# 2017_FDP_STRATEGIE.net
KiCad netlist of a schematic drawn in Altium Designer
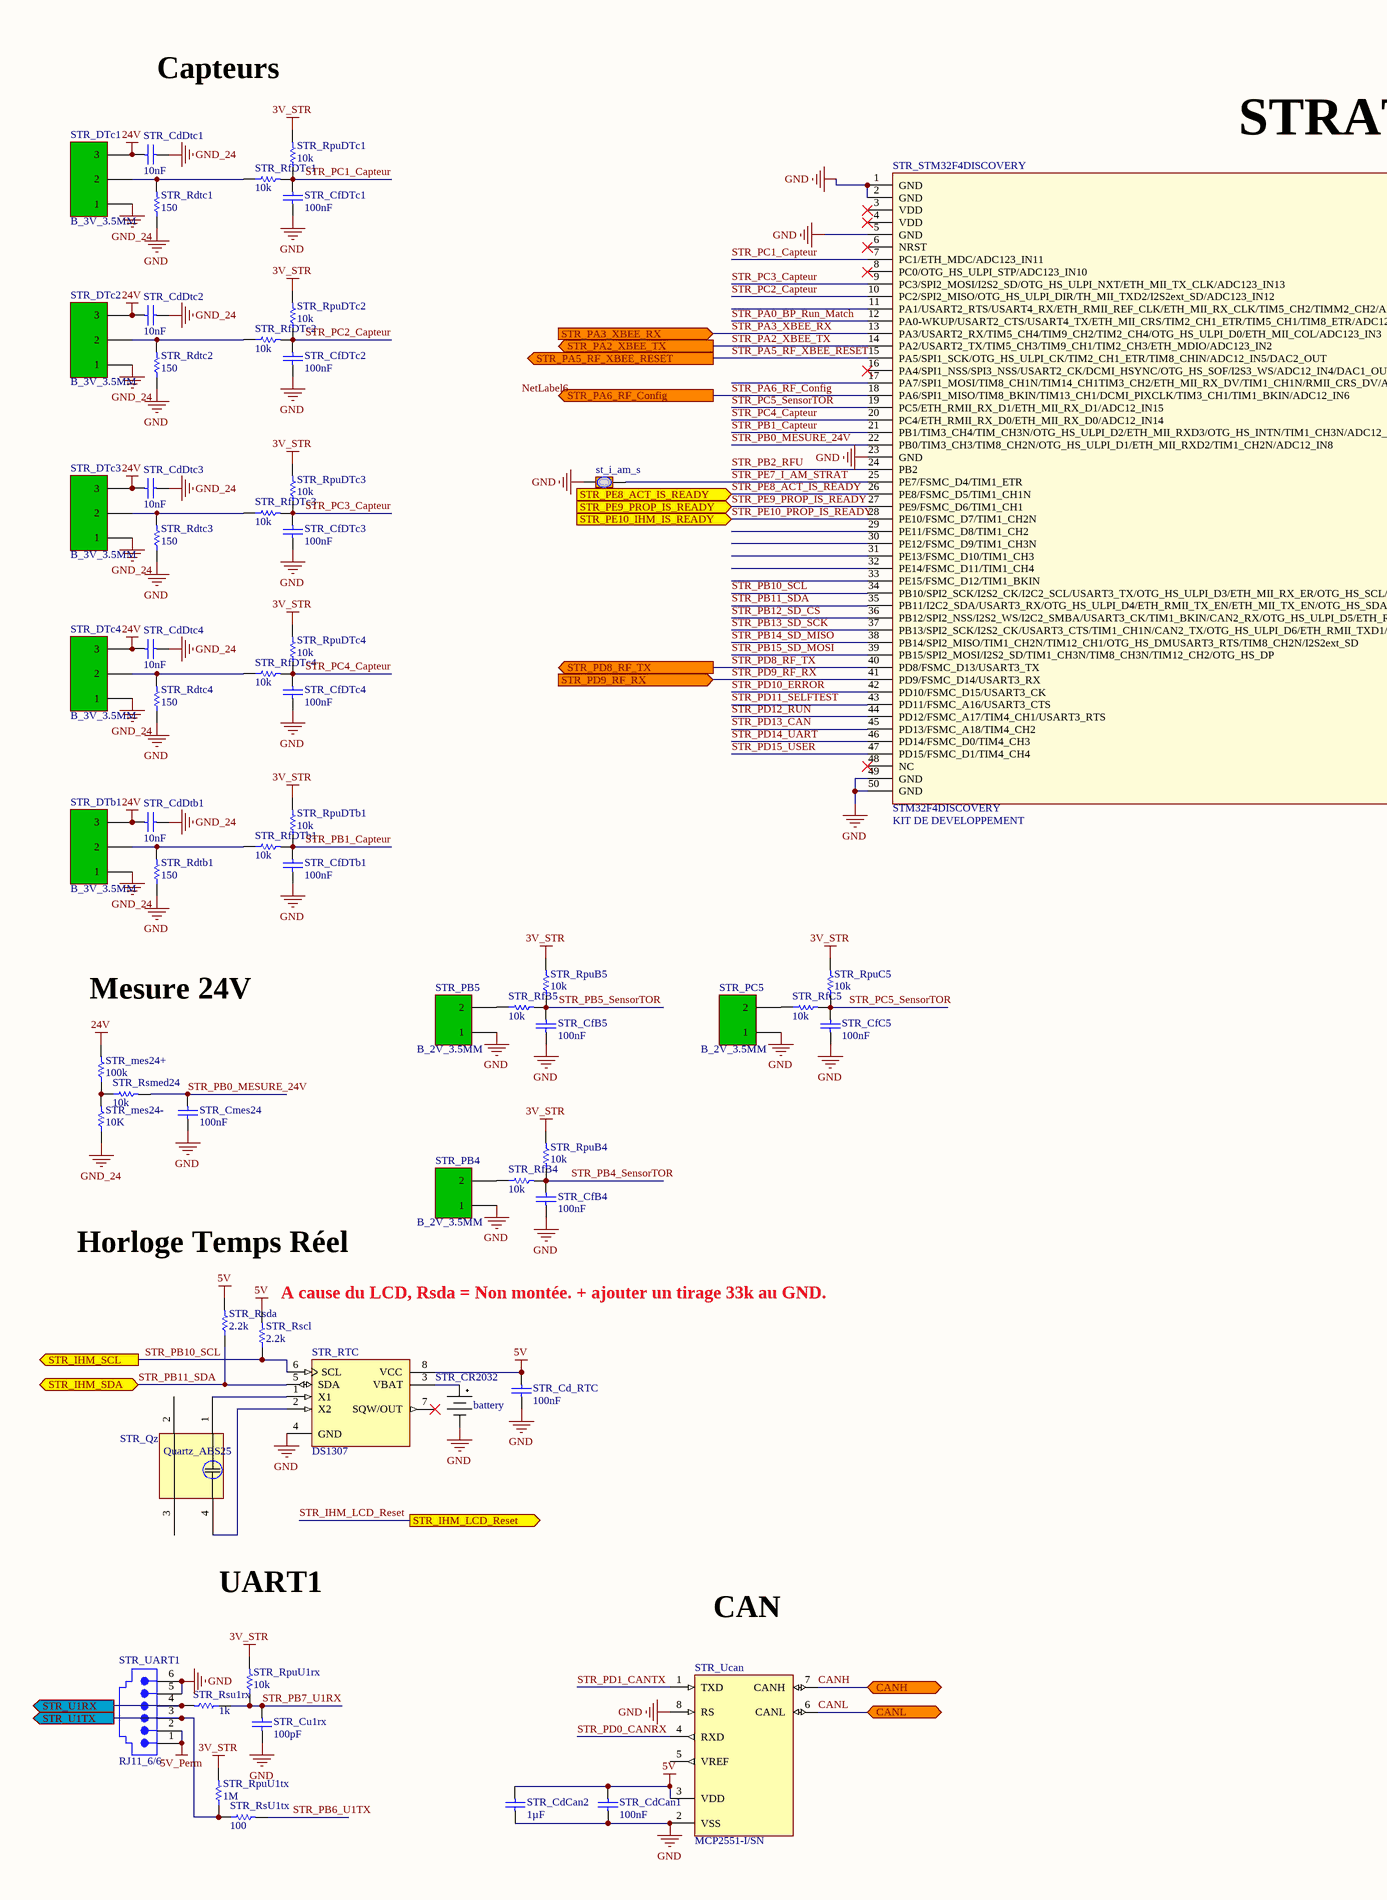
[diagram p0: 2017_FDP_STRATEGIE.SchDoc, left]
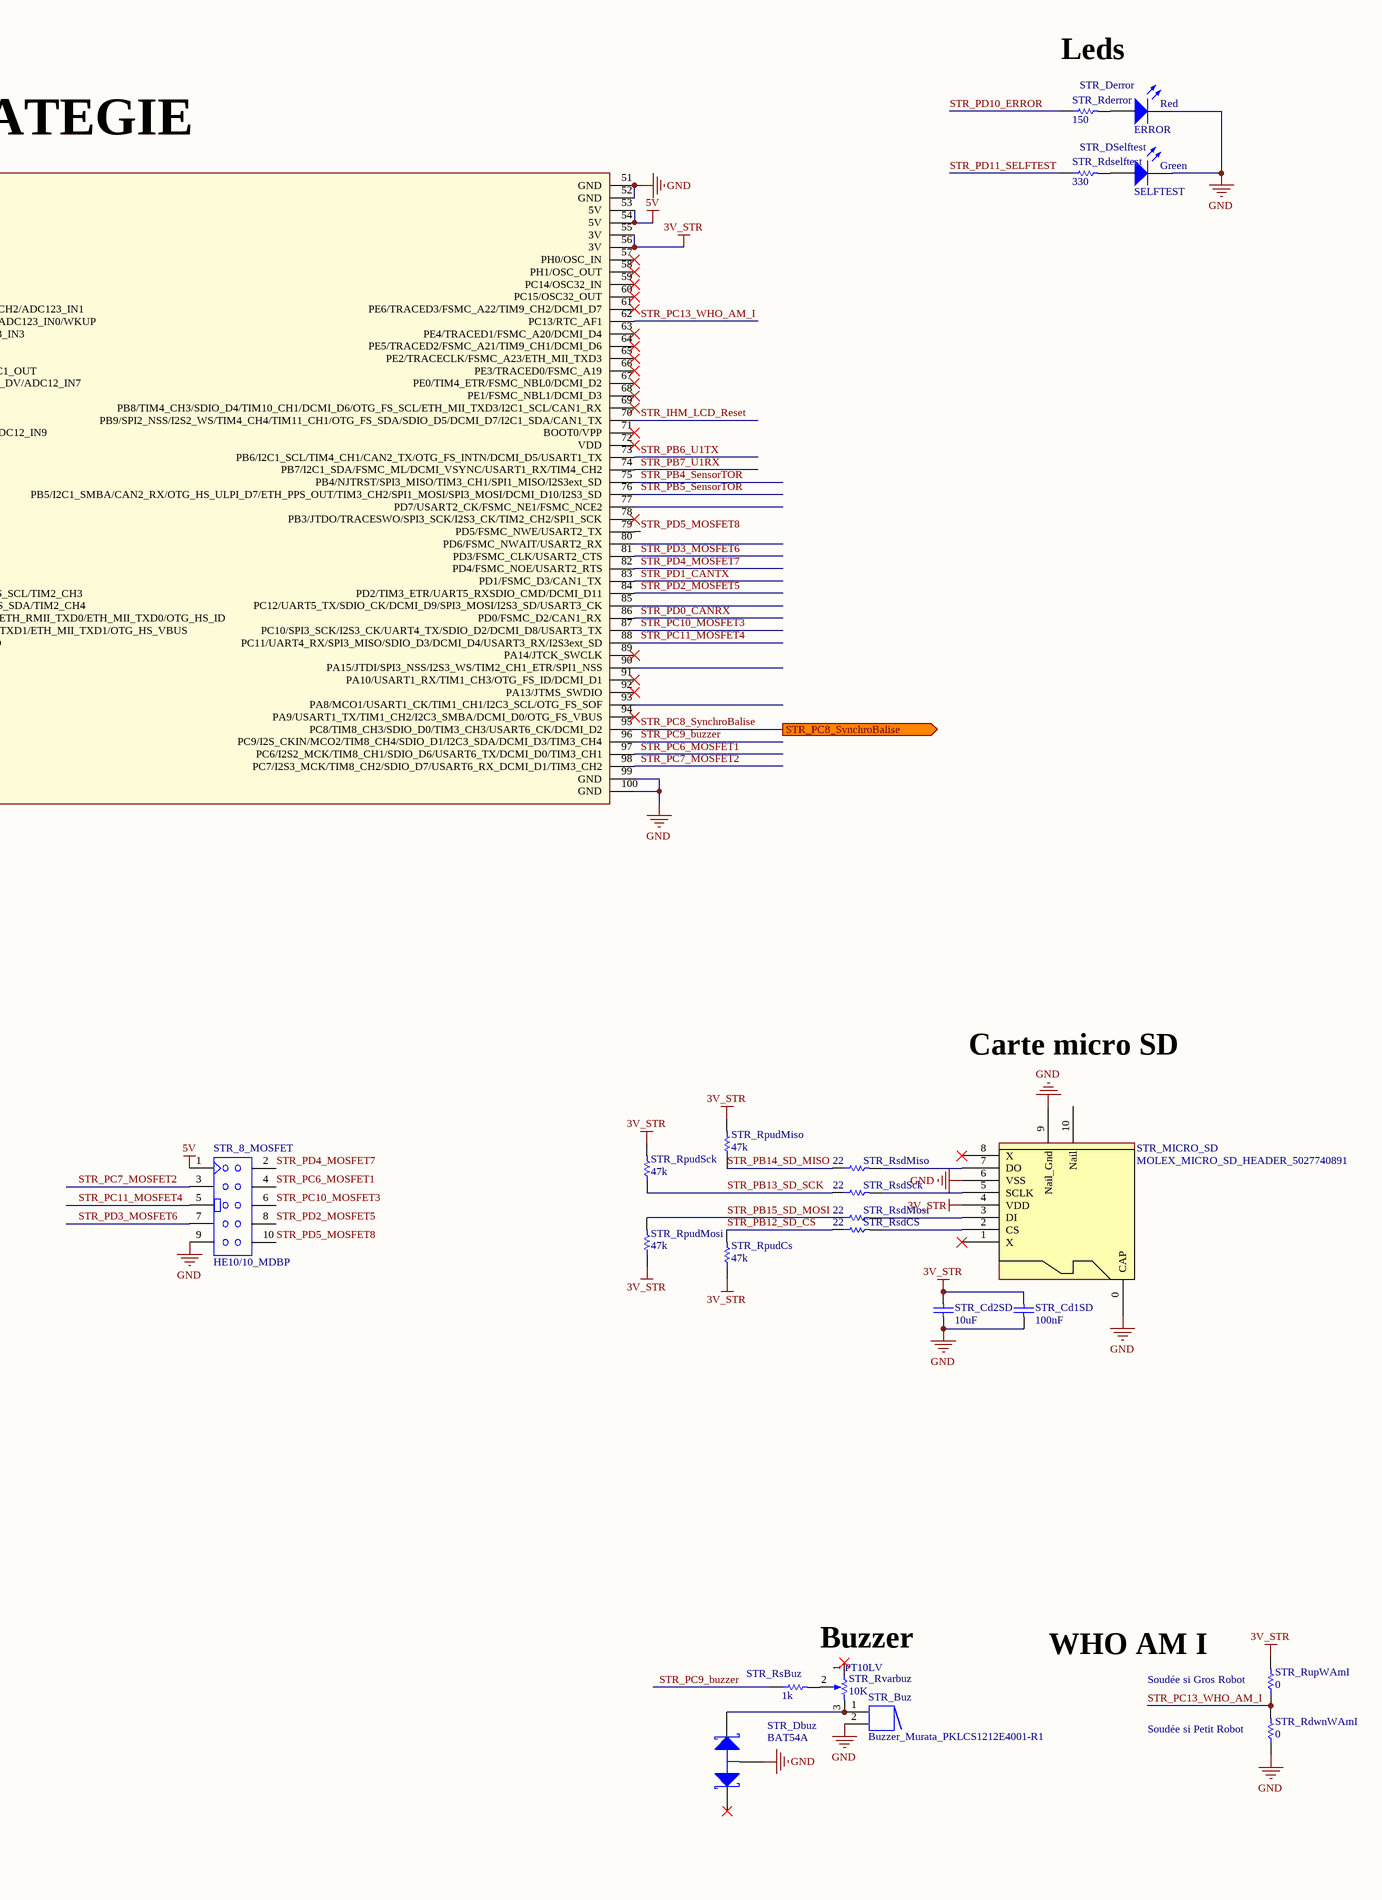
[diagram p1: 2017_FDP_STRATEGIE.SchDoc, right]

(export (version "E")
  (design (tool "Eeschema 10.0.6"))
  (components
    (comp (ref "STR_8_MOSFET")
      (value "HE10/10_MALE_DROIT_BAS_PROFIL")
      (footprint "HE10/10_M_D_BP")
      (description "EMBASE HE10/10 MALE DROIT BAS PROFIL")
      (fields (field (name "TYPE") "HE10/10_MDBP"))
      (libsource (lib "connecteurs") (part "HE10/10_MALE_DROIT_BAS_PROFIL"))
    )
    (comp (ref "STR_Buz")
      (value "Buzzer_Murata_PKLCS1212E4001-R1")
      (footprint "Buzzer_Murata PKLCS1212")
      (fields
        (field (name "MANUFACTURER") "MURATA")
        (field (name "MANUFACTURER PART NUMBER") "PKLCS1212E4001-R1")
      )
      (libsource (lib "DG_Buzzer") (part "Buzzer_Murata_PKLCS1212E4001-R1"))
    )
    (comp (ref "STR_Cd1SD")
      (value "100nF")
      (footprint "C0805_N")
      (description "Capacitor")
      (fields (field (name "PUBLISHER") "Altium Limited"))
      (libsource (lib "_ROBOT") (part "Condensateur"))
    )
    (comp (ref "STR_Cd2SD")
      (value "10uF")
      (footprint "C1206_N")
      (description "Capacitor")
      (fields (field (name "PUBLISHER") "Altium Limited"))
      (libsource (lib "_ROBOT") (part "Condensateur"))
    )
    (comp (ref "STR_CdCan1")
      (value "100nF")
      (footprint "C0805_N")
      (description "Capacitor")
      (fields (field (name "PUBLISHER") "Altium Limited"))
      (libsource (lib "_ROBOT") (part "Condensateur"))
    )
    (comp (ref "STR_CdCan2")
      (value "1µF")
      (footprint "C0805_N")
      (description "Capacitor")
      (fields (field (name "PUBLISHER") "Altium Limited"))
      (libsource (lib "_ROBOT") (part "Condensateur"))
    )
    (comp (ref "STR_CdDtb1")
      (value "10nF")
      (footprint "C0805_N")
      (description "Capacitor")
      (fields (field (name "PUBLISHER") "Altium Limited"))
      (libsource (lib "_ROBOT") (part "Condensateur"))
    )
    (comp (ref "STR_CdDtc1")
      (value "10nF")
      (footprint "C0805_N")
      (description "Capacitor")
      (fields (field (name "PUBLISHER") "Altium Limited"))
      (libsource (lib "_ROBOT") (part "Condensateur"))
    )
    (comp (ref "STR_CdDtc2")
      (value "10nF")
      (footprint "C0805_N")
      (description "Capacitor")
      (fields (field (name "PUBLISHER") "Altium Limited"))
      (libsource (lib "_ROBOT") (part "Condensateur"))
    )
    (comp (ref "STR_CdDtc3")
      (value "10nF")
      (footprint "C0805_N")
      (description "Capacitor")
      (fields (field (name "PUBLISHER") "Altium Limited"))
      (libsource (lib "_ROBOT") (part "Condensateur"))
    )
    (comp (ref "STR_CdDtc4")
      (value "10nF")
      (footprint "C0805_N")
      (description "Capacitor")
      (fields (field (name "PUBLISHER") "Altium Limited"))
      (libsource (lib "_ROBOT") (part "Condensateur"))
    )
    (comp (ref "STR_Cd_RTC")
      (value "100nF")
      (footprint "C0805_N")
      (description "Capacitor")
      (fields (field (name "PUBLISHER") "Altium Limited"))
      (libsource (lib "_ROBOT") (part "Condensateur"))
    )
    (comp (ref "STR_CfB4")
      (value "100nF")
      (footprint "C0805_N")
      (description "Capacitor")
      (fields (field (name "PUBLISHER") "Altium Limited"))
      (libsource (lib "_ROBOT") (part "Condensateur"))
    )
    (comp (ref "STR_CfB5")
      (value "100nF")
      (footprint "C0805_N")
      (description "Capacitor")
      (fields (field (name "PUBLISHER") "Altium Limited"))
      (libsource (lib "_ROBOT") (part "Condensateur"))
    )
    (comp (ref "STR_CfC5")
      (value "100nF")
      (footprint "C0805_N")
      (description "Capacitor")
      (fields (field (name "PUBLISHER") "Altium Limited"))
      (libsource (lib "_ROBOT") (part "Condensateur"))
    )
    (comp (ref "STR_CfDTb1")
      (value "100nF")
      (footprint "C0805_N")
      (description "Capacitor")
      (fields (field (name "PUBLISHER") "Altium Limited"))
      (libsource (lib "_ROBOT") (part "Condensateur"))
    )
    (comp (ref "STR_CfDTc1")
      (value "100nF")
      (footprint "C0805_N")
      (description "Capacitor")
      (fields (field (name "PUBLISHER") "Altium Limited"))
      (libsource (lib "_ROBOT") (part "Condensateur"))
    )
    (comp (ref "STR_CfDTc2")
      (value "100nF")
      (footprint "C0805_N")
      (description "Capacitor")
      (fields (field (name "PUBLISHER") "Altium Limited"))
      (libsource (lib "_ROBOT") (part "Condensateur"))
    )
    (comp (ref "STR_CfDTc3")
      (value "100nF")
      (footprint "C0805_N")
      (description "Capacitor")
      (fields (field (name "PUBLISHER") "Altium Limited"))
      (libsource (lib "_ROBOT") (part "Condensateur"))
    )
    (comp (ref "STR_CfDTc4")
      (value "100nF")
      (footprint "C0805_N")
      (description "Capacitor")
      (fields (field (name "PUBLISHER") "Altium Limited"))
      (libsource (lib "_ROBOT") (part "Condensateur"))
    )
    (comp (ref "STR_Cmes24")
      (value "100nF")
      (footprint "C0805_N")
      (description "Capacitor")
      (fields (field (name "PUBLISHER") "Altium Limited"))
      (libsource (lib "_ROBOT") (part "Condensateur"))
    )
    (comp (ref "STR_CR2032")
      (value "battery")
      (footprint "PILE_CR2032_Support_795 271 41_WURTH")
      (description "Battery, Pile")
      (fields (field (name "PUBLISHER") "Jean-Philippe Oudet"))
      (libsource (lib "LibPocketTag") (part "battery"))
    )
    (comp (ref "STR_Cu1rx")
      (value "100pF")
      (footprint "C0805_N")
      (description "Capacitor")
      (fields (field (name "PUBLISHER") "Altium Limited"))
      (libsource (lib "_ROBOT") (part "Condensateur"))
    )
    (comp (ref "STR_Dbuz")
      (value "BAT54A")
      (footprint "SOT23-3N")
      (description "DIODE SCHOTTKY DOUBLE")
      (fields (field (name "MANUFACTURER") "ZETEX"))
      (libsource (lib "_ROBOT") (part "Diode Shottky double  BAT54A"))
    )
    (comp (ref "STR_Derror")
      (value "ERROR")
      (footprint "LED_0805")
      (description "Typical LED")
      (fields (field (name "PUBLISHER") "Altium Limited"))
      (libsource (lib "_ROBOT") (part "LED"))
    )
    (comp (ref "STR_DSelftest")
      (value "SELFTEST")
      (footprint "LED_0805")
      (description "Typical LED")
      (fields (field (name "PUBLISHER") "Altium Limited"))
      (libsource (lib "_ROBOT") (part "LED"))
    )
    (comp (ref "STR_DTb1")
      (value "B_3V_3.5MM")
      (footprint "BORNIER_3V_3.5MM")
      (libsource (lib "Connecteur") (part "BORNIER_3V_3.5MM"))
    )
    (comp (ref "STR_DTc1")
      (value "B_3V_3.5MM")
      (footprint "BORNIER_3V_3.5MM")
      (libsource (lib "Connecteur") (part "BORNIER_3V_3.5MM"))
    )
    (comp (ref "STR_DTc2")
      (value "B_3V_3.5MM")
      (footprint "BORNIER_3V_3.5MM")
      (libsource (lib "Connecteur") (part "BORNIER_3V_3.5MM"))
    )
    (comp (ref "STR_DTc3")
      (value "B_3V_3.5MM")
      (footprint "BORNIER_3V_3.5MM")
      (libsource (lib "Connecteur") (part "BORNIER_3V_3.5MM"))
    )
    (comp (ref "STR_DTc4")
      (value "B_3V_3.5MM")
      (footprint "BORNIER_3V_3.5MM")
      (libsource (lib "Connecteur") (part "BORNIER_3V_3.5MM"))
    )
    (comp (ref "STR_mes24+")
      (value "100k")
      (footprint "R1206_N")
      (description "Resistor")
      (fields (field (name "PUBLISHER") "Altium Limited"))
      (libsource (lib "_ROBOT") (part "Resistor"))
    )
    (comp (ref "STR_mes24-")
      (value "10K")
      (footprint "R1206_N")
      (description "Resistor")
      (fields (field (name "PUBLISHER") "Altium Limited"))
      (libsource (lib "_ROBOT") (part "Resistor"))
    )
    (comp (ref "STR_MICRO_SD")
      (value "MOLEX_MICRO_SD_HEADER_5027740891")
      (footprint "MOLEX_MICRO_SD_HEADER_5027740891")
      (libsource (lib "Connecteur") (part "MOLEX_MICRO_SD_HEADER_5027740891"))
    )
    (comp (ref "STR_PB4")
      (value "B_2V_3.5MM")
      (footprint "BORNIER_2V_3.5MM")
      (libsource (lib "Connecteur") (part "BORNIER_2V_3.5MM"))
    )
    (comp (ref "STR_PB5")
      (value "B_2V_3.5MM")
      (footprint "BORNIER_2V_3.5MM")
      (libsource (lib "Connecteur") (part "BORNIER_2V_3.5MM"))
    )
    (comp (ref "STR_PC5")
      (value "B_2V_3.5MM")
      (footprint "BORNIER_2V_3.5MM")
      (libsource (lib "Connecteur") (part "BORNIER_2V_3.5MM"))
    )
    (comp (ref "STR_Qz")
      (value "Quartz_ABS25")
      (footprint "Quartz_ABS25")
      (libsource (lib "_ROBOT") (part "Quartz_ABS25"))
    )
    (comp (ref "STR_Rderror")
      (value "150")
      (footprint "R1206_N")
      (description "Resistor")
      (fields (field (name "PUBLISHER") "Altium Limited"))
      (libsource (lib "_ROBOT") (part "Resistor"))
    )
    (comp (ref "STR_Rdselftest")
      (value "330")
      (footprint "R1206_N")
      (description "Resistor")
      (fields (field (name "PUBLISHER") "Altium Limited"))
      (libsource (lib "_ROBOT") (part "Resistor"))
    )
    (comp (ref "STR_Rdtb1")
      (value "150")
      (footprint "R1206_N")
      (description "Resistor")
      (fields (field (name "PUBLISHER") "Altium Limited"))
      (libsource (lib "_ROBOT") (part "Resistor"))
    )
    (comp (ref "STR_Rdtc1")
      (value "150")
      (footprint "R1206_N")
      (description "Resistor")
      (fields (field (name "PUBLISHER") "Altium Limited"))
      (libsource (lib "_ROBOT") (part "Resistor"))
    )
    (comp (ref "STR_Rdtc2")
      (value "150")
      (footprint "R1206_N")
      (description "Resistor")
      (fields (field (name "PUBLISHER") "Altium Limited"))
      (libsource (lib "_ROBOT") (part "Resistor"))
    )
    (comp (ref "STR_Rdtc3")
      (value "150")
      (footprint "R1206_N")
      (description "Resistor")
      (fields (field (name "PUBLISHER") "Altium Limited"))
      (libsource (lib "_ROBOT") (part "Resistor"))
    )
    (comp (ref "STR_Rdtc4")
      (value "150")
      (footprint "R1206_N")
      (description "Resistor")
      (fields (field (name "PUBLISHER") "Altium Limited"))
      (libsource (lib "_ROBOT") (part "Resistor"))
    )
    (comp (ref "STR_RdwnWAmI")
      (value "0")
      (footprint "R1206_N")
      (description "Resistor")
      (fields (field (name "PUBLISHER") "Altium Limited"))
      (libsource (lib "_ROBOT") (part "Resistor"))
    )
    (comp (ref "STR_RfB4")
      (value "10k")
      (footprint "R1206_N")
      (description "Resistor")
      (fields (field (name "PUBLISHER") "Altium Limited"))
      (libsource (lib "_ROBOT") (part "Resistor"))
    )
    (comp (ref "STR_RfB5")
      (value "10k")
      (footprint "R1206_N")
      (description "Resistor")
      (fields (field (name "PUBLISHER") "Altium Limited"))
      (libsource (lib "_ROBOT") (part "Resistor"))
    )
    (comp (ref "STR_RfC5")
      (value "10k")
      (footprint "R1206_N")
      (description "Resistor")
      (fields (field (name "PUBLISHER") "Altium Limited"))
      (libsource (lib "_ROBOT") (part "Resistor"))
    )
    (comp (ref "STR_RfDTb1")
      (value "10k")
      (footprint "R1206_N")
      (description "Resistor")
      (fields (field (name "PUBLISHER") "Altium Limited"))
      (libsource (lib "_ROBOT") (part "Resistor"))
    )
    (comp (ref "STR_RfDTc1")
      (value "10k")
      (footprint "R1206_N")
      (description "Resistor")
      (fields (field (name "PUBLISHER") "Altium Limited"))
      (libsource (lib "_ROBOT") (part "Resistor"))
    )
    (comp (ref "STR_RfDTc2")
      (value "10k")
      (footprint "R1206_N")
      (description "Resistor")
      (fields (field (name "PUBLISHER") "Altium Limited"))
      (libsource (lib "_ROBOT") (part "Resistor"))
    )
    (comp (ref "STR_RfDTc3")
      (value "10k")
      (footprint "R1206_N")
      (description "Resistor")
      (fields (field (name "PUBLISHER") "Altium Limited"))
      (libsource (lib "_ROBOT") (part "Resistor"))
    )
    (comp (ref "STR_RfDTc4")
      (value "10k")
      (footprint "R1206_N")
      (description "Resistor")
      (fields (field (name "PUBLISHER") "Altium Limited"))
      (libsource (lib "_ROBOT") (part "Resistor"))
    )
    (comp (ref "STR_RpuB4")
      (value "10k")
      (footprint "R1206_N")
      (description "Resistor")
      (fields (field (name "PUBLISHER") "Altium Limited"))
      (libsource (lib "_ROBOT") (part "Resistor"))
    )
    (comp (ref "STR_RpuB5")
      (value "10k")
      (footprint "R1206_N")
      (description "Resistor")
      (fields (field (name "PUBLISHER") "Altium Limited"))
      (libsource (lib "_ROBOT") (part "Resistor"))
    )
    (comp (ref "STR_RpuC5")
      (value "10k")
      (footprint "R1206_N")
      (description "Resistor")
      (fields (field (name "PUBLISHER") "Altium Limited"))
      (libsource (lib "_ROBOT") (part "Resistor"))
    )
    (comp (ref "STR_RpudCs")
      (value "47k")
      (footprint "R1206_N")
      (description "Resistor")
      (fields (field (name "PUBLISHER") "Altium Limited"))
      (libsource (lib "_ROBOT") (part "Resistor"))
    )
    (comp (ref "STR_RpudMiso")
      (value "47k")
      (footprint "R1206_N")
      (description "Resistor")
      (fields (field (name "PUBLISHER") "Altium Limited"))
      (libsource (lib "_ROBOT") (part "Resistor"))
    )
    (comp (ref "STR_RpudMosi")
      (value "47k")
      (footprint "R1206_N")
      (description "Resistor")
      (fields (field (name "PUBLISHER") "Altium Limited"))
      (libsource (lib "_ROBOT") (part "Resistor"))
    )
    (comp (ref "STR_RpudSck")
      (value "47k")
      (footprint "R1206_N")
      (description "Resistor")
      (fields (field (name "PUBLISHER") "Altium Limited"))
      (libsource (lib "_ROBOT") (part "Resistor"))
    )
    (comp (ref "STR_RpuDTb1")
      (value "10k")
      (footprint "R1206_N")
      (description "Resistor")
      (fields (field (name "PUBLISHER") "Altium Limited"))
      (libsource (lib "_ROBOT") (part "Resistor"))
    )
    (comp (ref "STR_RpuDTc1")
      (value "10k")
      (footprint "R1206_N")
      (description "Resistor")
      (fields (field (name "PUBLISHER") "Altium Limited"))
      (libsource (lib "_ROBOT") (part "Resistor"))
    )
    (comp (ref "STR_RpuDTc2")
      (value "10k")
      (footprint "R1206_N")
      (description "Resistor")
      (fields (field (name "PUBLISHER") "Altium Limited"))
      (libsource (lib "_ROBOT") (part "Resistor"))
    )
    (comp (ref "STR_RpuDTc3")
      (value "10k")
      (footprint "R1206_N")
      (description "Resistor")
      (fields (field (name "PUBLISHER") "Altium Limited"))
      (libsource (lib "_ROBOT") (part "Resistor"))
    )
    (comp (ref "STR_RpuDTc4")
      (value "10k")
      (footprint "R1206_N")
      (description "Resistor")
      (fields (field (name "PUBLISHER") "Altium Limited"))
      (libsource (lib "_ROBOT") (part "Resistor"))
    )
    (comp (ref "STR_RpuU1rx")
      (value "10k")
      (footprint "R1206_N")
      (description "Resistor")
      (fields (field (name "PUBLISHER") "Altium Limited"))
      (libsource (lib "_ROBOT") (part "Resistor"))
    )
    (comp (ref "STR_RpuU1tx")
      (value "1M")
      (footprint "R1206_N")
      (description "Resistor")
      (fields (field (name "PUBLISHER") "Altium Limited"))
      (libsource (lib "_ROBOT") (part "Resistor"))
    )
    (comp (ref "STR_RsBuz")
      (value "1k")
      (footprint "R1206_N")
      (description "Resistor")
      (fields (field (name "PUBLISHER") "Altium Limited"))
      (libsource (lib "_ROBOT") (part "Resistor"))
    )
    (comp (ref "STR_Rscl")
      (value "2.2k")
      (footprint "R1206_N")
      (description "Resistor")
      (fields (field (name "PUBLISHER") "Altium Limited"))
      (libsource (lib "_ROBOT") (part "Resistor"))
    )
    (comp (ref "STR_Rsda")
      (value "2.2k")
      (footprint "R1206_N")
      (description "Resistor")
      (fields (field (name "PUBLISHER") "Altium Limited"))
      (libsource (lib "_ROBOT") (part "Resistor"))
    )
    (comp (ref "STR_RsdCS")
      (value "22")
      (footprint "R1206_N")
      (description "Resistor")
      (fields (field (name "PUBLISHER") "Altium Limited"))
      (libsource (lib "_ROBOT") (part "Resistor"))
    )
    (comp (ref "STR_RsdMiso")
      (value "22")
      (footprint "R1206_N")
      (description "Resistor")
      (fields (field (name "PUBLISHER") "Altium Limited"))
      (libsource (lib "_ROBOT") (part "Resistor"))
    )
    (comp (ref "STR_RsdMosi")
      (value "22")
      (footprint "R1206_N")
      (description "Resistor")
      (fields (field (name "PUBLISHER") "Altium Limited"))
      (libsource (lib "_ROBOT") (part "Resistor"))
    )
    (comp (ref "STR_RsdSck")
      (value "22")
      (footprint "R1206_N")
      (description "Resistor")
      (fields (field (name "PUBLISHER") "Altium Limited"))
      (libsource (lib "_ROBOT") (part "Resistor"))
    )
    (comp (ref "STR_Rsmed24")
      (value "10k")
      (footprint "R1206_N")
      (description "Resistor")
      (fields (field (name "PUBLISHER") "Altium Limited"))
      (libsource (lib "_ROBOT") (part "Resistor"))
    )
    (comp (ref "STR_Rsu1rx")
      (value "1k")
      (footprint "R1206_N")
      (description "Resistor")
      (fields (field (name "PUBLISHER") "Altium Limited"))
      (libsource (lib "_ROBOT") (part "Resistor"))
    )
    (comp (ref "STR_RsU1tx")
      (value "100")
      (footprint "R1206_N")
      (description "Resistor")
      (fields (field (name "PUBLISHER") "Altium Limited"))
      (libsource (lib "_ROBOT") (part "Resistor"))
    )
    (comp (ref "STR_RTC")
      (value "DS1307")
      (footprint "SO8_N")
      (description "64 X 8 Serial Real-Time Clock")
      (fields (field (name "PUBLISHER") "Altium Limited"))
      (libsource (lib "Robot2010") (part "DS1307"))
    )
    (comp (ref "STR_RupWAmI")
      (value "0")
      (footprint "R1206_N")
      (description "Resistor")
      (fields (field (name "PUBLISHER") "Altium Limited"))
      (libsource (lib "_ROBOT") (part "Resistor"))
    )
    (comp (ref "STR_Rvarbuz")
      (value "10K")
      (footprint "TRIMMER_MONOTOUR_PT10LV")
      (description "RESISTANCE VARIABLE_TRAVERSANTE : PT10LV")
      (fields
        (field (name "TYPE") "PT10LV")
        (field (name "Comment") "RESISTANCE_VARIABLE_TRAVERSANTE : PT10LV")
      )
      (libsource (lib "composants passifs") (part "RESISTANCE_VARIABLE_TRAVERSANTE {colon} PT10LV"))
    )
    (comp (ref "STR_STM32F4DISCOVERY")
      (value "STM32F4DISCOVERY")
      (footprint "STM32_F4DISCOVERY")
      (description "KIT DE DEVELOPPEMENT POUR MICROCONTROLEUR STM32F407VGT6")
      (fields (field (name "TYPE") "KIT DE DEVELOPPEMENT"))
      (libsource (lib "circuits integres") (part "STM32F4DISCOVERY"))
    )
    (comp (ref "STR_UART1")
      (value "RJ11_6/6")
      (footprint "RJ11_6/6 - droit")
      (description "Right Angle, Standard Profile, Offset Latch DECconnect, Flangeless PCB Jack")
      (fields (field (name "PUBLISHER") "Altium Limited"))
      (libsource (lib "Connecteur") (part "RJ11_6/6"))
    )
    (comp (ref "STR_Ucan")
      (value "MCP2551-I/SN")
      (footprint "SO8_N")
      (description "High-Speed CAN Transceiver, 8-Pin SOIC, Industrial Temperature")
      (fields (field (name "PUBLISHER") "Damien Guitton"))
      (libsource (lib "Circuit intégré") (part "MCP2551-I/SN"))
    )
    (comp (ref "st_i_am_s")
      (value "Goutte Strap_2")
      (footprint "Goutte Strap_2 Pads_Clearance 0.254mm")
      (fields (field (name "PUBLISHER") "Damien Guitton"))
      (libsource (lib "DG_Connecteur") (part "Goutte Strap_2"))
    )
  )
  (nets
    (net (code "1") (name "/CANH") (class "Default")
      (node (ref "STR_Ucan") (pin "7") (pinfunction "CANH_7") (pintype "bidirectional"))
    )
    (net (code "2") (name "/CANL") (class "Default")
      (node (ref "STR_Ucan") (pin "6") (pinfunction "CANL_6") (pintype "bidirectional"))
    )
    (net (code "4") (name "/STR_IHM_LCD_Reset") (class "Default")
      (node (ref "STR_STM32F4DISCOVERY") (pin "70") (pinfunction "PB9/SPI2_NSS/I2S2_WS/TIM4_CH4/TIM11_CH1/OTG_FS_SDA/SDIO_D5/DCMI_D7/I2C1_SDA/CAN1_TX_70") (pintype "passive"))
    )
    (net (code "5") (name "/STR_PA0_BP_Run_Match") (class "Default")
      (node (ref "STR_STM32F4DISCOVERY") (pin "12") (pinfunction "PA0-WKUP/USART2_CTS/USART4_TX/ETH_MII_CRS/TIM2_CH1_ETR/TIM5_CH1/TIM8_ETR/ADC123_IN0/WKUP_12") (pintype "passive"))
    )
    (net (code "6") (name "/STR_PA2_XBEE_TX") (class "Default")
      (node (ref "STR_STM32F4DISCOVERY") (pin "14") (pinfunction "PA2/USART2_TX/TIM5_CH3/TIM9_CH1/TIM2_CH3/ETH_MDIO/ADC123_IN2_14") (pintype "passive"))
    )
    (net (code "7") (name "/STR_PA3_XBEE_RX") (class "Default")
      (node (ref "STR_STM32F4DISCOVERY") (pin "13") (pinfunction "PA3/USART2_RX/TIM5_CH4/TIM9_CH2/TIM2_CH4/OTG_HS_ULPI_D0/ETH_MII_COL/ADC123_IN3_13") (pintype "passive"))
    )
    (net (code "8") (name "/STR_PA5_RF_XBEE_RESET") (class "Default")
      (node (ref "STR_STM32F4DISCOVERY") (pin "15") (pinfunction "PA5/SPI1_SCK/OTG_HS_ULPI_CK/TIM2_CH1_ETR/TIM8_CHIN/ADC12_IN5/DAC2_OUT_15") (pintype "passive"))
    )
    (net (code "9") (name "/STR_PA6_RF_Config") (class "Default")
      (node (ref "STR_STM32F4DISCOVERY") (pin "18") (pinfunction "PA6/SPI1_MISO/TIM8_BKIN/TIM13_CH1/DCMI_PIXCLK/TIM3_CH1/TIM1_BKIN/ADC12_IN6_18") (pintype "passive"))
    )
    (net (code "10") (name "/STR_PB0_MESURE_24V") (class "Default")
      (node (ref "STR_Cmes24") (pin "2") (pinfunction "2_2") (pintype "passive"))
      (node (ref "STR_Rsmed24") (pin "2") (pinfunction "2_2") (pintype "passive"))
      (node (ref "STR_STM32F4DISCOVERY") (pin "22") (pinfunction "PB0/TIM3_CH3/TIM8_CH2N/OTG_HS_ULPI_D1/ETH_MII_RXD2/TIM1_CH2N/ADC12_IN8_22") (pintype "passive"))
    )
    (net (code "11") (name "/STR_PB1_Capteur") (class "Default")
      (node (ref "STR_CfDTb1") (pin "2") (pinfunction "2_2") (pintype "passive"))
      (node (ref "STR_RfDTb1") (pin "2") (pinfunction "2_2") (pintype "passive"))
      (node (ref "STR_RpuDTb1") (pin "1") (pinfunction "1_1") (pintype "passive"))
      (node (ref "STR_STM32F4DISCOVERY") (pin "21") (pinfunction "PB1/TIM3_CH4/TIM_CH3N/OTG_HS_ULPI_D2/ETH_MII_RXD3/OTG_HS_INTN/TIM1_CH3N/ADC12_IN9_21") (pintype "passive"))
    )
    (net (code "12") (name "/STR_PB2_RFU") (class "Default")
      (node (ref "STR_STM32F4DISCOVERY") (pin "24") (pinfunction "PB2_24") (pintype "passive"))
    )
    (net (code "13") (name "/STR_PB4_SensorTOR") (class "Default")
      (node (ref "STR_CfB4") (pin "2") (pinfunction "2_2") (pintype "passive"))
      (node (ref "STR_RfB4") (pin "2") (pinfunction "2_2") (pintype "passive"))
      (node (ref "STR_RpuB4") (pin "1") (pinfunction "1_1") (pintype "passive"))
      (node (ref "STR_STM32F4DISCOVERY") (pin "75") (pinfunction "PB4/NJTRST/SPI3_MISO/TIM3_CH1/SPI1_MISO/I2S3ext_SD_75") (pintype "passive"))
    )
    (net (code "14") (name "/STR_PB5_SensorTOR") (class "Default")
      (node (ref "STR_CfB5") (pin "2") (pinfunction "2_2") (pintype "passive"))
      (node (ref "STR_RfB5") (pin "2") (pinfunction "2_2") (pintype "passive"))
      (node (ref "STR_RpuB5") (pin "1") (pinfunction "1_1") (pintype "passive"))
      (node (ref "STR_STM32F4DISCOVERY") (pin "76") (pinfunction "PB5/I2C1_SMBA/CAN2_RX/OTG_HS_ULPI_D7/ETH_PPS_OUT/TIM3_CH2/SPI1_MOSI/SPI3_MOSI/DCMI_D10/I2S3_SD_76") (pintype "passive"))
    )
    (net (code "15") (name "/STR_PB6_U1TX") (class "Default")
      (node (ref "STR_RsU1tx") (pin "2") (pinfunction "2_2") (pintype "passive"))
      (node (ref "STR_STM32F4DISCOVERY") (pin "73") (pinfunction "PB6/I2C1_SCL/TIM4_CH1/CAN2_TX/OTG_FS_INTN/DCMI_D5/USART1_TX_73") (pintype "passive"))
    )
    (net (code "16") (name "/STR_PB7_U1RX") (class "Default")
      (node (ref "STR_Cu1rx") (pin "2") (pinfunction "2_2") (pintype "passive"))
      (node (ref "STR_RpuU1rx") (pin "1") (pinfunction "1_1") (pintype "passive"))
      (node (ref "STR_Rsu1rx") (pin "1") (pinfunction "1_1") (pintype "passive"))
      (node (ref "STR_STM32F4DISCOVERY") (pin "74") (pinfunction "PB7/I2C1_SDA/FSMC_ML/DCMI_VSYNC/USART1_RX/TIM4_CH2_74") (pintype "passive"))
    )
    (net (code "17") (name "/STR_PB10_SCL") (class "Default")
      (node (ref "STR_RTC") (pin "6") (pinfunction "SCL_6") (pintype "input"))
      (node (ref "STR_Rscl") (pin "1") (pinfunction "1_1") (pintype "passive"))
      (node (ref "STR_STM32F4DISCOVERY") (pin "34") (pinfunction "PB10/SPI2_SCK/I2S2_CK/I2C2_SCL/USART3_TX/OTG_HS_ULPI_D3/ETH_MII_RX_ER/OTG_HS_SCL/TIM2_CH3_34") (pintype "passive"))
    )
    (net (code "18") (name "/STR_PB11_SDA") (class "Default")
      (node (ref "STR_RTC") (pin "5") (pinfunction "SDA_5") (pintype "bidirectional"))
      (node (ref "STR_Rsda") (pin "1") (pinfunction "1_1") (pintype "passive"))
      (node (ref "STR_STM32F4DISCOVERY") (pin "35") (pinfunction "PB11/I2C2_SDA/USART3_RX/OTG_HS_ULPI_D4/ETH_RMII_TX_EN/ETH_MII_TX_EN/OTG_HS_SDA/TIM2_CH4_35") (pintype "passive"))
    )
    (net (code "19") (name "/STR_PB12_SD_CS") (class "Default")
      (node (ref "STR_RpudCs") (pin "2") (pinfunction "2_2") (pintype "passive"))
      (node (ref "STR_RsdCS") (pin "1") (pinfunction "1_1") (pintype "passive"))
      (node (ref "STR_STM32F4DISCOVERY") (pin "36") (pinfunction "PB12/SPI2_NSS/I2S2_WS/I2C2_SMBA/USART3_CK/TIM1_BKIN/CAN2_RX/OTG_HS_ULPI_D5/ETH_RMII_TXD0/ETH_MII_TXD0/OTG_HS_ID_36") (pintype "passive"))
    )
    (net (code "20") (name "/STR_PB13_SD_SCK") (class "Default")
      (node (ref "STR_RpudSck") (pin "1") (pinfunction "1_1") (pintype "passive"))
      (node (ref "STR_RsdSck") (pin "1") (pinfunction "1_1") (pintype "passive"))
      (node (ref "STR_STM32F4DISCOVERY") (pin "37") (pinfunction "PB13/SPI2_SCK/I2S2_CK/USART3_CTS/TIM1_CH1N/CAN2_TX/OTG_HS_ULPI_D6/ETH_RMII_TXD1/ETH_MII_TXD1/OTG_HS_VBUS_37") (pintype "passive"))
    )
    (net (code "21") (name "/STR_PB14_SD_MISO") (class "Default")
      (node (ref "STR_RpudMiso") (pin "1") (pinfunction "1_1") (pintype "passive"))
      (node (ref "STR_RsdMiso") (pin "1") (pinfunction "1_1") (pintype "passive"))
      (node (ref "STR_STM32F4DISCOVERY") (pin "38") (pinfunction "PB14/SPI2_MISO/TIM1_CH2N/TIM12_CH1/OTG_HS_DMUSART3_RTS/TIM8_CH2N/I2S2ext_SD_38") (pintype "passive"))
    )
    (net (code "22") (name "/STR_PB15_SD_MOSI") (class "Default")
      (node (ref "STR_RpudMosi") (pin "2") (pinfunction "2_2") (pintype "passive"))
      (node (ref "STR_RsdMosi") (pin "1") (pinfunction "1_1") (pintype "passive"))
      (node (ref "STR_STM32F4DISCOVERY") (pin "39") (pinfunction "PB15/SPI2_MOSI/I2S2_SD/TIM1_CH3N/TIM8_CH3N/TIM12_CH2/OTG_HS_DP_39") (pintype "passive"))
    )
    (net (code "23") (name "/STR_PC1_Capteur") (class "Default")
      (node (ref "STR_CfDTc1") (pin "2") (pinfunction "2_2") (pintype "passive"))
      (node (ref "STR_RfDTc1") (pin "2") (pinfunction "2_2") (pintype "passive"))
      (node (ref "STR_RpuDTc1") (pin "1") (pinfunction "1_1") (pintype "passive"))
      (node (ref "STR_STM32F4DISCOVERY") (pin "7") (pinfunction "PC1/ETH_MDC/ADC123_IN11_7") (pintype "passive"))
    )
    (net (code "24") (name "/STR_PC2_Capteur") (class "Default")
      (node (ref "STR_CfDTc2") (pin "2") (pinfunction "2_2") (pintype "passive"))
      (node (ref "STR_RfDTc2") (pin "2") (pinfunction "2_2") (pintype "passive"))
      (node (ref "STR_RpuDTc2") (pin "1") (pinfunction "1_1") (pintype "passive"))
      (node (ref "STR_STM32F4DISCOVERY") (pin "10") (pinfunction "PC2/SPI2_MISO/OTG_HS_ULPI_DIR/TH_MII_TXD2/I2S2ext_SD/ADC123_IN12_10") (pintype "passive"))
    )
    (net (code "25") (name "/STR_PC3_Capteur") (class "Default")
      (node (ref "STR_CfDTc3") (pin "2") (pinfunction "2_2") (pintype "passive"))
      (node (ref "STR_RfDTc3") (pin "2") (pinfunction "2_2") (pintype "passive"))
      (node (ref "STR_RpuDTc3") (pin "1") (pinfunction "1_1") (pintype "passive"))
      (node (ref "STR_STM32F4DISCOVERY") (pin "9") (pinfunction "PC3/SPI2_MOSI/I2S2_SD/OTG_HS_ULPI_NXT/ETH_MII_TX_CLK/ADC123_IN13_9") (pintype "passive"))
    )
    (net (code "26") (name "/STR_PC4_Capteur") (class "Default")
      (node (ref "STR_CfDTc4") (pin "2") (pinfunction "2_2") (pintype "passive"))
      (node (ref "STR_RfDTc4") (pin "2") (pinfunction "2_2") (pintype "passive"))
      (node (ref "STR_RpuDTc4") (pin "1") (pinfunction "1_1") (pintype "passive"))
      (node (ref "STR_STM32F4DISCOVERY") (pin "20") (pinfunction "PC4/ETH_RMII_RX_D0/ETH_MII_RX_D0/ADC12_IN14_20") (pintype "passive"))
    )
    (net (code "27") (name "/STR_PC5_SensorTOR") (class "Default")
      (node (ref "STR_CfC5") (pin "2") (pinfunction "2_2") (pintype "passive"))
      (node (ref "STR_RfC5") (pin "2") (pinfunction "2_2") (pintype "passive"))
      (node (ref "STR_RpuC5") (pin "1") (pinfunction "1_1") (pintype "passive"))
      (node (ref "STR_STM32F4DISCOVERY") (pin "19") (pinfunction "PC5/ETH_RMII_RX_D1/ETH_MII_RX_D1/ADC12_IN15_19") (pintype "passive"))
    )
    (net (code "28") (name "/STR_PC6_MOSFET1") (class "Default")
      (node (ref "STR_8_MOSFET") (pin "4") (pinfunction "4_4") (pintype "passive"))
      (node (ref "STR_STM32F4DISCOVERY") (pin "97") (pinfunction "PC6/I2S2_MCK/TIM8_CH1/SDIO_D6/USART6_TX/DCMI_D0/TIM3_CH1_97") (pintype "passive"))
    )
    (net (code "29") (name "/STR_PC7_MOSFET2") (class "Default")
      (node (ref "STR_8_MOSFET") (pin "3") (pinfunction "3_3") (pintype "passive"))
      (node (ref "STR_STM32F4DISCOVERY") (pin "98") (pinfunction "PC7/I2S3_MCK/TIM8_CH2/SDIO_D7/USART6_RX_DCMI_D1/TIM3_CH2_98") (pintype "passive"))
    )
    (net (code "30") (name "/STR_PC8_SynchroBalise") (class "Default")
      (node (ref "STR_STM32F4DISCOVERY") (pin "95") (pinfunction "PC8/TIM8_CH3/SDIO_D0/TIM3_CH3/USART6_CK/DCMI_D2_95") (pintype "passive"))
    )
    (net (code "31") (name "/STR_PC9_buzzer") (class "Default")
      (node (ref "STR_RsBuz") (pin "1") (pinfunction "1_1") (pintype "passive"))
      (node (ref "STR_STM32F4DISCOVERY") (pin "96") (pinfunction "PC9/I2S_CKIN/MCO2/TIM8_CH4/SDIO_D1/I2C3_SDA/DCMI_D3/TIM3_CH4_96") (pintype "passive"))
    )
    (net (code "32") (name "/STR_PC10_MOSFET3") (class "Default")
      (node (ref "STR_8_MOSFET") (pin "6") (pinfunction "6_6") (pintype "passive"))
      (node (ref "STR_STM32F4DISCOVERY") (pin "87") (pinfunction "PC10/SPI3_SCK/I2S3_CK/UART4_TX/SDIO_D2/DCMI_D8/USART3_TX_87") (pintype "passive"))
    )
    (net (code "33") (name "/STR_PC11_MOSFET4") (class "Default")
      (node (ref "STR_8_MOSFET") (pin "5") (pinfunction "5_5") (pintype "passive"))
      (node (ref "STR_STM32F4DISCOVERY") (pin "88") (pinfunction "PC11/UART4_RX/SPI3_MISO/SDIO_D3/DCMI_D4/USART3_RX/I2S3ext_SD_88") (pintype "passive"))
    )
    (net (code "34") (name "/STR_PC13_WHO_AM_I") (class "Default")
      (node (ref "STR_RdwnWAmI") (pin "2") (pinfunction "2_2") (pintype "passive"))
      (node (ref "STR_RupWAmI") (pin "1") (pinfunction "1_1") (pintype "passive"))
      (node (ref "STR_STM32F4DISCOVERY") (pin "62") (pinfunction "PC13/RTC_AF1_62") (pintype "passive"))
    )
    (net (code "35") (name "/STR_PD0_CANRX") (class "Default")
      (node (ref "STR_STM32F4DISCOVERY") (pin "86") (pinfunction "PD0/FSMC_D2/CAN1_RX_86") (pintype "passive"))
      (node (ref "STR_Ucan") (pin "4") (pinfunction "RXD_4") (pintype "output"))
    )
    (net (code "36") (name "/STR_PD1_CANTX") (class "Default")
      (node (ref "STR_STM32F4DISCOVERY") (pin "83") (pinfunction "PD1/FSMC_D3/CAN1_TX_83") (pintype "passive"))
      (node (ref "STR_Ucan") (pin "1") (pinfunction "TXD_1") (pintype "input"))
    )
    (net (code "37") (name "/STR_PD2_MOSFET5") (class "Default")
      (node (ref "STR_8_MOSFET") (pin "8") (pinfunction "8_8") (pintype "passive"))
      (node (ref "STR_STM32F4DISCOVERY") (pin "84") (pinfunction "PD2/TIM3_ETR/UART5_RXSDIO_CMD/DCMI_D11_84") (pintype "passive"))
    )
    (net (code "38") (name "/STR_PD3_MOSFET6") (class "Default")
      (node (ref "STR_8_MOSFET") (pin "7") (pinfunction "7_7") (pintype "passive"))
      (node (ref "STR_STM32F4DISCOVERY") (pin "81") (pinfunction "PD3/FSMC_CLK/USART2_CTS_81") (pintype "passive"))
    )
    (net (code "39") (name "/STR_PD4_MOSFET7") (class "Default")
      (node (ref "STR_8_MOSFET") (pin "2") (pinfunction "2_2") (pintype "passive"))
      (node (ref "STR_STM32F4DISCOVERY") (pin "82") (pinfunction "PD4/FSMC_NOE/USART2_RTS_82") (pintype "passive"))
    )
    (net (code "40") (name "/STR_PD5_MOSFET8") (class "Default")
      (node (ref "STR_8_MOSFET") (pin "10") (pinfunction "10_10") (pintype "passive"))
      (node (ref "STR_STM32F4DISCOVERY") (pin "79") (pinfunction "PD5/FSMC_NWE/USART2_TX_79") (pintype "passive"))
    )
    (net (code "41") (name "/STR_PD8_RF_TX") (class "Default")
      (node (ref "STR_STM32F4DISCOVERY") (pin "40") (pinfunction "PD8/FSMC_D13/USART3_TX_40") (pintype "passive"))
    )
    (net (code "42") (name "/STR_PD9_RF_RX") (class "Default")
      (node (ref "STR_STM32F4DISCOVERY") (pin "41") (pinfunction "PD9/FSMC_D14/USART3_RX_41") (pintype "passive"))
    )
    (net (code "43") (name "/STR_PD10_ERROR") (class "Default")
      (node (ref "STR_Rderror") (pin "1") (pinfunction "1_1") (pintype "passive"))
      (node (ref "STR_STM32F4DISCOVERY") (pin "42") (pinfunction "PD10/FSMC_D15/USART3_CK_42") (pintype "passive"))
    )
    (net (code "44") (name "/STR_PD11_SELFTEST") (class "Default")
      (node (ref "STR_Rdselftest") (pin "1") (pinfunction "1_1") (pintype "passive"))
      (node (ref "STR_STM32F4DISCOVERY") (pin "43") (pinfunction "PD11/FSMC_A16/USART3_CTS_43") (pintype "passive"))
    )
    (net (code "45") (name "/STR_PD12_RUN") (class "Default")
      (node (ref "STR_STM32F4DISCOVERY") (pin "44") (pinfunction "PD12/FSMC_A17/TIM4_CH1/USART3_RTS_44") (pintype "passive"))
    )
    (net (code "46") (name "/STR_PD13_CAN") (class "Default")
      (node (ref "STR_STM32F4DISCOVERY") (pin "45") (pinfunction "PD13/FSMC_A18/TIM4_CH2_45") (pintype "passive"))
    )
    (net (code "47") (name "/STR_PD14_UART") (class "Default")
      (node (ref "STR_STM32F4DISCOVERY") (pin "46") (pinfunction "PD14/FSMC_D0/TIM4_CH3_46") (pintype "passive"))
    )
    (net (code "48") (name "/STR_PD15_USER") (class "Default")
      (node (ref "STR_STM32F4DISCOVERY") (pin "47") (pinfunction "PD15/FSMC_D1/TIM4_CH4_47") (pintype "passive"))
    )
    (net (code "49") (name "/STR_PE7_I_AM_STRAT") (class "Default")
      (node (ref "STR_STM32F4DISCOVERY") (pin "25") (pinfunction "PE7/FSMC_D4/TIM1_ETR_25") (pintype "passive"))
      (node (ref "st_i_am_s") (pin "2") (pinfunction "2_2") (pintype "passive"))
    )
    (net (code "50") (name "/STR_PE8_ACT_IS_READY") (class "Default")
      (node (ref "STR_STM32F4DISCOVERY") (pin "26") (pinfunction "PE8/FSMC_D5/TIM1_CH1N_26") (pintype "passive"))
    )
    (net (code "51") (name "/STR_PE9_PROP_IS_READY") (class "Default")
      (node (ref "STR_STM32F4DISCOVERY") (pin "27") (pinfunction "PE9/FSMC_D6/TIM1_CH1_27") (pintype "passive"))
    )
    (net (code "52") (name "/STR_PE10_PROP_IS_READY") (class "Default")
      (node (ref "STR_STM32F4DISCOVERY") (pin "28") (pinfunction "PE10/FSMC_D7/TIM1_CH2N_28") (pintype "passive"))
    )
    (net (code "53") (name "/STR_U1RX") (class "Default")
      (node (ref "STR_Rsu1rx") (pin "2") (pinfunction "2_2") (pintype "passive"))
      (node (ref "STR_UART1") (pin "4") (pinfunction "4_4") (pintype "passive"))
    )
    (net (code "54") (name "/STR_U1TX") (class "Default")
      (node (ref "STR_RpuU1tx") (pin "1") (pinfunction "1_1") (pintype "passive"))
      (node (ref "STR_RsU1tx") (pin "1") (pinfunction "1_1") (pintype "passive"))
      (node (ref "STR_UART1") (pin "3") (pinfunction "3_3") (pintype "passive"))
    )
    (net (code "55") (name "3V_STR") (class "Default")
      (node (ref "STR_Cd1SD") (pin "2") (pinfunction "2_2") (pintype "passive"))
      (node (ref "STR_Cd2SD") (pin "2") (pinfunction "2_2") (pintype "passive"))
      (node (ref "STR_MICRO_SD") (pin "4") (pinfunction "VDD_4") (pintype "passive"))
      (node (ref "STR_RpuB4") (pin "2") (pinfunction "2_2") (pintype "passive"))
      (node (ref "STR_RpuB5") (pin "2") (pinfunction "2_2") (pintype "passive"))
      (node (ref "STR_RpuC5") (pin "2") (pinfunction "2_2") (pintype "passive"))
      (node (ref "STR_RpuDTb1") (pin "2") (pinfunction "2_2") (pintype "passive"))
      (node (ref "STR_RpuDTc1") (pin "2") (pinfunction "2_2") (pintype "passive"))
      (node (ref "STR_RpuDTc2") (pin "2") (pinfunction "2_2") (pintype "passive"))
      (node (ref "STR_RpuDTc3") (pin "2") (pinfunction "2_2") (pintype "passive"))
      (node (ref "STR_RpuDTc4") (pin "2") (pinfunction "2_2") (pintype "passive"))
      (node (ref "STR_RpuU1rx") (pin "2") (pinfunction "2_2") (pintype "passive"))
      (node (ref "STR_RpuU1tx") (pin "2") (pinfunction "2_2") (pintype "passive"))
      (node (ref "STR_RpudCs") (pin "1") (pinfunction "1_1") (pintype "passive"))
      (node (ref "STR_RpudMiso") (pin "2") (pinfunction "2_2") (pintype "passive"))
      (node (ref "STR_RpudMosi") (pin "1") (pinfunction "1_1") (pintype "passive"))
      (node (ref "STR_RpudSck") (pin "2") (pinfunction "2_2") (pintype "passive"))
      (node (ref "STR_RupWAmI") (pin "2") (pinfunction "2_2") (pintype "passive"))
      (node (ref "STR_STM32F4DISCOVERY") (pin "55") (pinfunction "3V_55") (pintype "passive"))
      (node (ref "STR_STM32F4DISCOVERY") (pin "56") (pinfunction "3V_56") (pintype "passive"))
    )
    (net (code "56") (name "5V") (class "Default")
      (node (ref "STR_8_MOSFET") (pin "1") (pinfunction "1_1") (pintype "passive"))
      (node (ref "STR_CdCan1") (pin "2") (pinfunction "2_2") (pintype "passive"))
      (node (ref "STR_CdCan2") (pin "2") (pinfunction "2_2") (pintype "passive"))
      (node (ref "STR_Cd_RTC") (pin "1") (pinfunction "1_1") (pintype "passive"))
      (node (ref "STR_RTC") (pin "8") (pinfunction "VCC_8") (pintype "power_in"))
      (node (ref "STR_Rscl") (pin "2") (pinfunction "2_2") (pintype "passive"))
      (node (ref "STR_Rsda") (pin "2") (pinfunction "2_2") (pintype "passive"))
      (node (ref "STR_STM32F4DISCOVERY") (pin "53") (pinfunction "5V_53") (pintype "passive"))
      (node (ref "STR_STM32F4DISCOVERY") (pin "54") (pinfunction "5V_54") (pintype "passive"))
      (node (ref "STR_Ucan") (pin "3") (pinfunction "VDD_3") (pintype "power_in"))
    )
    (net (code "57") (name "5V_Perm") (class "Default")
      (node (ref "STR_UART1") (pin "1") (pinfunction "1_1") (pintype "passive"))
      (node (ref "STR_UART1") (pin "2") (pinfunction "2_2") (pintype "passive"))
    )
    (net (code "58") (name "24V") (class "Default")
      (node (ref "STR_CdDtb1") (pin "2") (pinfunction "2_2") (pintype "passive"))
      (node (ref "STR_CdDtc1") (pin "2") (pinfunction "2_2") (pintype "passive"))
      (node (ref "STR_CdDtc2") (pin "2") (pinfunction "2_2") (pintype "passive"))
      (node (ref "STR_CdDtc3") (pin "2") (pinfunction "2_2") (pintype "passive"))
      (node (ref "STR_CdDtc4") (pin "2") (pinfunction "2_2") (pintype "passive"))
      (node (ref "STR_DTb1") (pin "3") (pinfunction "3_3") (pintype "passive"))
      (node (ref "STR_DTc1") (pin "3") (pinfunction "3_3") (pintype "passive"))
      (node (ref "STR_DTc2") (pin "3") (pinfunction "3_3") (pintype "passive"))
      (node (ref "STR_DTc3") (pin "3") (pinfunction "3_3") (pintype "passive"))
      (node (ref "STR_DTc4") (pin "3") (pinfunction "3_3") (pintype "passive"))
      (node (ref "STR_mes24+") (pin "2") (pinfunction "2_2") (pintype "passive"))
    )
    (net (code "59") (name "GND") (class "Default")
      (node (ref "STR_8_MOSFET") (pin "9") (pinfunction "9_9") (pintype "passive"))
      (node (ref "STR_Buz") (pin "2") (pinfunction "2_2") (pintype "passive"))
      (node (ref "STR_CR2032") (pin "-") (pinfunction "-_-") (pintype "power_in"))
      (node (ref "STR_Cd1SD") (pin "1") (pinfunction "1_1") (pintype "passive"))
      (node (ref "STR_Cd2SD") (pin "1") (pinfunction "1_1") (pintype "passive"))
      (node (ref "STR_CdCan1") (pin "1") (pinfunction "1_1") (pintype "passive"))
      (node (ref "STR_CdCan2") (pin "1") (pinfunction "1_1") (pintype "passive"))
      (node (ref "STR_Cd_RTC") (pin "2") (pinfunction "2_2") (pintype "passive"))
      (node (ref "STR_CfB4") (pin "1") (pinfunction "1_1") (pintype "passive"))
      (node (ref "STR_CfB5") (pin "1") (pinfunction "1_1") (pintype "passive"))
      (node (ref "STR_CfC5") (pin "1") (pinfunction "1_1") (pintype "passive"))
      (node (ref "STR_CfDTb1") (pin "1") (pinfunction "1_1") (pintype "passive"))
      (node (ref "STR_CfDTc1") (pin "1") (pinfunction "1_1") (pintype "passive"))
      (node (ref "STR_CfDTc2") (pin "1") (pinfunction "1_1") (pintype "passive"))
      (node (ref "STR_CfDTc3") (pin "1") (pinfunction "1_1") (pintype "passive"))
      (node (ref "STR_CfDTc4") (pin "1") (pinfunction "1_1") (pintype "passive"))
      (node (ref "STR_Cmes24") (pin "1") (pinfunction "1_1") (pintype "passive"))
      (node (ref "STR_Cu1rx") (pin "1") (pinfunction "1_1") (pintype "passive"))
      (node (ref "STR_DSelftest") (pin "2") (pinfunction "K_2") (pintype "passive"))
      (node (ref "STR_Dbuz") (pin "3") (pinfunction "A_3") (pintype "passive"))
      (node (ref "STR_Derror") (pin "2") (pinfunction "K_2") (pintype "passive"))
      (node (ref "STR_MICRO_SD") (pin "0") (pinfunction "CAP_0") (pintype "passive"))
      (node (ref "STR_MICRO_SD") (pin "6") (pinfunction "VSS_6") (pintype "passive"))
      (node (ref "STR_MICRO_SD") (pin "9") (pinfunction "Nail_Gnd_9") (pintype "passive"))
      (node (ref "STR_PB4") (pin "1") (pinfunction "1_1") (pintype "passive"))
      (node (ref "STR_PB5") (pin "1") (pinfunction "1_1") (pintype "passive"))
      (node (ref "STR_PC5") (pin "1") (pinfunction "1_1") (pintype "passive"))
      (node (ref "STR_RTC") (pin "4") (pinfunction "GND_4") (pintype "power_in"))
      (node (ref "STR_Rdtb1") (pin "1") (pinfunction "1_1") (pintype "passive"))
      (node (ref "STR_Rdtc1") (pin "1") (pinfunction "1_1") (pintype "passive"))
      (node (ref "STR_Rdtc2") (pin "1") (pinfunction "1_1") (pintype "passive"))
      (node (ref "STR_Rdtc3") (pin "1") (pinfunction "1_1") (pintype "passive"))
      (node (ref "STR_Rdtc4") (pin "1") (pinfunction "1_1") (pintype "passive"))
      (node (ref "STR_RdwnWAmI") (pin "1") (pinfunction "1_1") (pintype "passive"))
      (node (ref "STR_STM32F4DISCOVERY") (pin "1") (pinfunction "GND_1") (pintype "passive"))
      (node (ref "STR_STM32F4DISCOVERY") (pin "100") (pinfunction "GND_100") (pintype "passive"))
      (node (ref "STR_STM32F4DISCOVERY") (pin "2") (pinfunction "GND_2") (pintype "passive"))
      (node (ref "STR_STM32F4DISCOVERY") (pin "23") (pinfunction "GND_23") (pintype "passive"))
      (node (ref "STR_STM32F4DISCOVERY") (pin "49") (pinfunction "GND_49") (pintype "passive"))
      (node (ref "STR_STM32F4DISCOVERY") (pin "5") (pinfunction "GND_5") (pintype "passive"))
      (node (ref "STR_STM32F4DISCOVERY") (pin "50") (pinfunction "GND_50") (pintype "passive"))
      (node (ref "STR_STM32F4DISCOVERY") (pin "51") (pinfunction "GND_51") (pintype "passive"))
      (node (ref "STR_STM32F4DISCOVERY") (pin "52") (pinfunction "GND_52") (pintype "passive"))
      (node (ref "STR_STM32F4DISCOVERY") (pin "99") (pinfunction "GND_99") (pintype "passive"))
      (node (ref "STR_UART1") (pin "5") (pinfunction "5_5") (pintype "passive"))
      (node (ref "STR_UART1") (pin "6") (pinfunction "6_6") (pintype "passive"))
      (node (ref "STR_Ucan") (pin "2") (pinfunction "VSS_2") (pintype "power_in"))
      (node (ref "STR_Ucan") (pin "8") (pinfunction "RS_8") (pintype "input"))
      (node (ref "st_i_am_s") (pin "1") (pinfunction "1_1") (pintype "passive"))
    )
    (net (code "60") (name "GND_24") (class "Default")
      (node (ref "STR_CdDtb1") (pin "1") (pinfunction "1_1") (pintype "passive"))
      (node (ref "STR_CdDtc1") (pin "1") (pinfunction "1_1") (pintype "passive"))
      (node (ref "STR_CdDtc2") (pin "1") (pinfunction "1_1") (pintype "passive"))
      (node (ref "STR_CdDtc3") (pin "1") (pinfunction "1_1") (pintype "passive"))
      (node (ref "STR_CdDtc4") (pin "1") (pinfunction "1_1") (pintype "passive"))
      (node (ref "STR_DTb1") (pin "1") (pinfunction "1_1") (pintype "passive"))
      (node (ref "STR_DTc1") (pin "1") (pinfunction "1_1") (pintype "passive"))
      (node (ref "STR_DTc2") (pin "1") (pinfunction "1_1") (pintype "passive"))
      (node (ref "STR_DTc3") (pin "1") (pinfunction "1_1") (pintype "passive"))
      (node (ref "STR_DTc4") (pin "1") (pinfunction "1_1") (pintype "passive"))
      (node (ref "STR_mes24-") (pin "1") (pinfunction "1_1") (pintype "passive"))
    )
    (net (code "61") (name "Net-(STR_DSelftest-A)") (class "Default")
      (node (ref "STR_DSelftest") (pin "1") (pinfunction "A_1") (pintype "passive"))
      (node (ref "STR_Rdselftest") (pin "2") (pinfunction "2_2") (pintype "passive"))
    )
    (net (code "62") (name "Net-(STR_DTb1-Pad2)") (class "Default")
      (node (ref "STR_DTb1") (pin "2") (pinfunction "2_2") (pintype "passive"))
      (node (ref "STR_Rdtb1") (pin "2") (pinfunction "2_2") (pintype "passive"))
      (node (ref "STR_RfDTb1") (pin "1") (pinfunction "1_1") (pintype "passive"))
    )
    (net (code "63") (name "Net-(STR_DTc1-Pad2)") (class "Default")
      (node (ref "STR_DTc1") (pin "2") (pinfunction "2_2") (pintype "passive"))
      (node (ref "STR_Rdtc1") (pin "2") (pinfunction "2_2") (pintype "passive"))
      (node (ref "STR_RfDTc1") (pin "1") (pinfunction "1_1") (pintype "passive"))
    )
    (net (code "64") (name "Net-(STR_DTc2-Pad2)") (class "Default")
      (node (ref "STR_DTc2") (pin "2") (pinfunction "2_2") (pintype "passive"))
      (node (ref "STR_Rdtc2") (pin "2") (pinfunction "2_2") (pintype "passive"))
      (node (ref "STR_RfDTc2") (pin "1") (pinfunction "1_1") (pintype "passive"))
    )
    (net (code "65") (name "Net-(STR_DTc3-Pad2)") (class "Default")
      (node (ref "STR_DTc3") (pin "2") (pinfunction "2_2") (pintype "passive"))
      (node (ref "STR_Rdtc3") (pin "2") (pinfunction "2_2") (pintype "passive"))
      (node (ref "STR_RfDTc3") (pin "1") (pinfunction "1_1") (pintype "passive"))
    )
    (net (code "66") (name "Net-(STR_DTc4-Pad2)") (class "Default")
      (node (ref "STR_DTc4") (pin "2") (pinfunction "2_2") (pintype "passive"))
      (node (ref "STR_Rdtc4") (pin "2") (pinfunction "2_2") (pintype "passive"))
      (node (ref "STR_RfDTc4") (pin "1") (pinfunction "1_1") (pintype "passive"))
    )
    (net (code "67") (name "Net-(STR_Dbuz-K1)") (class "Default")
      (node (ref "STR_Buz") (pin "1") (pinfunction "1_1") (pintype "passive"))
      (node (ref "STR_Dbuz") (pin "1") (pinfunction "K1_1") (pintype "passive"))
      (node (ref "STR_Rvarbuz") (pin "3") (pinfunction "3_3") (pintype "passive"))
    )
    (net (code "68") (name "Net-(STR_Derror-A)") (class "Default")
      (node (ref "STR_Derror") (pin "1") (pinfunction "A_1") (pintype "passive"))
      (node (ref "STR_Rderror") (pin "2") (pinfunction "2_2") (pintype "passive"))
    )
    (net (code "69") (name "Net-(STR_MICRO_SD-CS)") (class "Default")
      (node (ref "STR_MICRO_SD") (pin "2") (pinfunction "CS_2") (pintype "passive"))
      (node (ref "STR_RsdCS") (pin "2") (pinfunction "2_2") (pintype "passive"))
    )
    (net (code "70") (name "Net-(STR_MICRO_SD-DI)") (class "Default")
      (node (ref "STR_MICRO_SD") (pin "3") (pinfunction "DI_3") (pintype "passive"))
      (node (ref "STR_RsdMosi") (pin "2") (pinfunction "2_2") (pintype "passive"))
    )
    (net (code "71") (name "Net-(STR_MICRO_SD-DO)") (class "Default")
      (node (ref "STR_MICRO_SD") (pin "7") (pinfunction "DO_7") (pintype "passive"))
      (node (ref "STR_RsdMiso") (pin "2") (pinfunction "2_2") (pintype "passive"))
    )
    (net (code "72") (name "Net-(STR_MICRO_SD-SCLK)") (class "Default")
      (node (ref "STR_MICRO_SD") (pin "5") (pinfunction "SCLK_5") (pintype "passive"))
      (node (ref "STR_RsdSck") (pin "2") (pinfunction "2_2") (pintype "passive"))
    )
    (net (code "73") (name "Net-(STR_PB4-Pad2)") (class "Default")
      (node (ref "STR_PB4") (pin "2") (pinfunction "2_2") (pintype "passive"))
      (node (ref "STR_RfB4") (pin "1") (pinfunction "1_1") (pintype "passive"))
    )
    (net (code "74") (name "Net-(STR_PB5-Pad2)") (class "Default")
      (node (ref "STR_PB5") (pin "2") (pinfunction "2_2") (pintype "passive"))
      (node (ref "STR_RfB5") (pin "1") (pinfunction "1_1") (pintype "passive"))
    )
    (net (code "75") (name "Net-(STR_PC5-Pad2)") (class "Default")
      (node (ref "STR_PC5") (pin "2") (pinfunction "2_2") (pintype "passive"))
      (node (ref "STR_RfC5") (pin "1") (pinfunction "1_1") (pintype "passive"))
    )
    (net (code "76") (name "Net-(STR_RTC-VBAT)") (class "Default")
      (node (ref "STR_CR2032") (pin "+") (pinfunction "+_+") (pintype "power_in"))
      (node (ref "STR_RTC") (pin "3") (pinfunction "VBAT_3") (pintype "power_in"))
    )
    (net (code "77") (name "Net-(STR_RTC-X1)") (class "Default")
      (node (ref "STR_Qz") (pin "1") (pinfunction "1_1") (pintype "passive"))
      (node (ref "STR_RTC") (pin "1") (pinfunction "X1_1") (pintype "input"))
    )
    (net (code "78") (name "Net-(STR_RTC-X2)") (class "Default")
      (node (ref "STR_Qz") (pin "4") (pinfunction "4_4") (pintype "passive"))
      (node (ref "STR_RTC") (pin "2") (pinfunction "X2_2") (pintype "input"))
    )
    (net (code "79") (name "Net-(STR_RsBuz-Pad2)") (class "Default")
      (node (ref "STR_RsBuz") (pin "2") (pinfunction "2_2") (pintype "passive"))
      (node (ref "STR_Rvarbuz") (pin "2") (pinfunction "2_2") (pintype "passive"))
    )
    (net (code "80") (name "Net-(STR_Rsmed24-Pad1)") (class "Default")
      (node (ref "STR_Rsmed24") (pin "1") (pinfunction "1_1") (pintype "passive"))
      (node (ref "STR_mes24+") (pin "1") (pinfunction "1_1") (pintype "passive"))
      (node (ref "STR_mes24-") (pin "2") (pinfunction "2_2") (pintype "passive"))
    )
    (net (code "81") (name "unconnected-(STR_Dbuz-K2-Pad2)") (class "Default")
      (node (ref "STR_Dbuz") (pin "2") (pinfunction "K2_2") (pintype "passive+no_connect"))
    )
    (net (code "82") (name "unconnected-(STR_MICRO_SD-Nail-Pad10)") (class "Default")
      (node (ref "STR_MICRO_SD") (pin "10") (pinfunction "Nail_10") (pintype "passive"))
    )
    (net (code "83") (name "unconnected-(STR_MICRO_SD-X-Pad1)") (class "Default")
      (node (ref "STR_MICRO_SD") (pin "1") (pinfunction "X_1") (pintype "passive+no_connect"))
    )
    (net (code "84") (name "unconnected-(STR_MICRO_SD-X-Pad8)") (class "Default")
      (node (ref "STR_MICRO_SD") (pin "8") (pinfunction "X_8") (pintype "passive+no_connect"))
    )
    (net (code "85") (name "unconnected-(STR_Qz-Pad2)") (class "Default")
      (node (ref "STR_Qz") (pin "2") (pinfunction "2_2") (pintype "passive"))
    )
    (net (code "86") (name "unconnected-(STR_Qz-Pad3)") (class "Default")
      (node (ref "STR_Qz") (pin "3") (pinfunction "3_3") (pintype "passive"))
    )
    (net (code "87") (name "unconnected-(STR_RTC-SQW{slash}OUT-Pad7)") (class "Default")
      (node (ref "STR_RTC") (pin "7") (pinfunction "SQW/OUT_7") (pintype "output+no_connect"))
    )
    (net (code "88") (name "unconnected-(STR_Rvarbuz-Pad1)") (class "Default")
      (node (ref "STR_Rvarbuz") (pin "1") (pinfunction "1_1") (pintype "passive+no_connect"))
    )
    (net (code "89") (name "unconnected-(STR_STM32F4DISCOVERY-BOOT0{slash}VPP-Pad71)") (class "Default")
      (node (ref "STR_STM32F4DISCOVERY") (pin "71") (pinfunction "BOOT0/VPP_71") (pintype "passive+no_connect"))
    )
    (net (code "90") (name "unconnected-(STR_STM32F4DISCOVERY-NC-Pad48)") (class "Default")
      (node (ref "STR_STM32F4DISCOVERY") (pin "48") (pinfunction "NC_48") (pintype "passive+no_connect"))
    )
    (net (code "91") (name "unconnected-(STR_STM32F4DISCOVERY-NRST-Pad6)") (class "Default")
      (node (ref "STR_STM32F4DISCOVERY") (pin "6") (pinfunction "NRST_6") (pintype "passive+no_connect"))
    )
    (net (code "92") (name "unconnected-(STR_STM32F4DISCOVERY-PA1{slash}USART2_RTS{slash}USART4_RX{slash}ETH_RMII_REF_CLK{slash}ETH_MII_RX_CLK{slash}TIM5_CH2{slash}TIMM2_CH2{slash}ADC123_IN1-Pad11)") (class "Default")
      (node (ref "STR_STM32F4DISCOVERY") (pin "11") (pinfunction "PA1/USART2_RTS/USART4_RX/ETH_RMII_REF_CLK/ETH_MII_RX_CLK/TIM5_CH2/TIMM2_CH2/ADC123_IN1_11") (pintype "passive"))
    )
    (net (code "93") (name "unconnected-(STR_STM32F4DISCOVERY-PA4{slash}SPI1_NSS{slash}SPI3_NSS{slash}USART2_CK{slash}DCMI_HSYNC{slash}OTG_HS_SOF{slash}I2S3_WS{slash}ADC12_IN4{slash}DAC1_OUT-Pad16)") (class "Default")
      (node (ref "STR_STM32F4DISCOVERY") (pin "16") (pinfunction "PA4/SPI1_NSS/SPI3_NSS/USART2_CK/DCMI_HSYNC/OTG_HS_SOF/I2S3_WS/ADC12_IN4/DAC1_OUT_16") (pintype "passive+no_connect"))
    )
    (net (code "94") (name "unconnected-(STR_STM32F4DISCOVERY-PA7{slash}SPI1_MOSI{slash}TIM8_CH1N{slash}TIM14_CH1TIM3_CH2{slash}ETH_MII_RX_DV{slash}TIM1_CH1N{slash}RMII_CRS_DV{slash}ADC12_IN7-Pad17)") (class "Default")
      (node (ref "STR_STM32F4DISCOVERY") (pin "17") (pinfunction "PA7/SPI1_MOSI/TIM8_CH1N/TIM14_CH1TIM3_CH2/ETH_MII_RX_DV/TIM1_CH1N/RMII_CRS_DV/ADC12_IN7_17") (pintype "passive"))
    )
    (net (code "95") (name "unconnected-(STR_STM32F4DISCOVERY-PA8{slash}MCO1{slash}USART1_CK{slash}TIM1_CH1{slash}I2C3_SCL{slash}OTG_FS_SOF-Pad93)") (class "Default")
      (node (ref "STR_STM32F4DISCOVERY") (pin "93") (pinfunction "PA8/MCO1/USART1_CK/TIM1_CH1/I2C3_SCL/OTG_FS_SOF_93") (pintype "passive"))
    )
    (net (code "96") (name "unconnected-(STR_STM32F4DISCOVERY-PA9{slash}USART1_TX{slash}TIM1_CH2{slash}I2C3_SMBA{slash}DCMI_D0{slash}OTG_FS_VBUS-Pad94)") (class "Default")
      (node (ref "STR_STM32F4DISCOVERY") (pin "94") (pinfunction "PA9/USART1_TX/TIM1_CH2/I2C3_SMBA/DCMI_D0/OTG_FS_VBUS_94") (pintype "passive+no_connect"))
    )
    (net (code "97") (name "unconnected-(STR_STM32F4DISCOVERY-PA10{slash}USART1_RX{slash}TIM1_CH3{slash}OTG_FS_ID{slash}DCMI_D1-Pad91)") (class "Default")
      (node (ref "STR_STM32F4DISCOVERY") (pin "91") (pinfunction "PA10/USART1_RX/TIM1_CH3/OTG_FS_ID/DCMI_D1_91") (pintype "passive+no_connect"))
    )
    (net (code "98") (name "unconnected-(STR_STM32F4DISCOVERY-PA13{slash}JTMS_SWDIO-Pad92)") (class "Default")
      (node (ref "STR_STM32F4DISCOVERY") (pin "92") (pinfunction "PA13/JTMS_SWDIO_92") (pintype "passive+no_connect"))
    )
    (net (code "99") (name "unconnected-(STR_STM32F4DISCOVERY-PA14{slash}JTCK_SWCLK-Pad89)") (class "Default")
      (node (ref "STR_STM32F4DISCOVERY") (pin "89") (pinfunction "PA14/JTCK_SWCLK_89") (pintype "passive+no_connect"))
    )
    (net (code "100") (name "unconnected-(STR_STM32F4DISCOVERY-PA15{slash}JTDI{slash}SPI3_NSS{slash}I2S3_WS{slash}TIM2_CH1_ETR{slash}SPI1_NSS-Pad90)") (class "Default")
      (node (ref "STR_STM32F4DISCOVERY") (pin "90") (pinfunction "PA15/JTDI/SPI3_NSS/I2S3_WS/TIM2_CH1_ETR/SPI1_NSS_90") (pintype "passive"))
    )
    (net (code "101") (name "unconnected-(STR_STM32F4DISCOVERY-PB3{slash}JTDO{slash}TRACESWO{slash}SPI3_SCK{slash}I2S3_CK{slash}TIM2_CH2{slash}SPI1_SCK-Pad78)") (class "Default")
      (node (ref "STR_STM32F4DISCOVERY") (pin "78") (pinfunction "PB3/JTDO/TRACESWO/SPI3_SCK/I2S3_CK/TIM2_CH2/SPI1_SCK_78") (pintype "passive+no_connect"))
    )
    (net (code "102") (name "unconnected-(STR_STM32F4DISCOVERY-PB8{slash}TIM4_CH3{slash}SDIO_D4{slash}TIM10_CH1{slash}DCMI_D6{slash}OTG_FS_SCL{slash}ETH_MII_TXD3{slash}I2C1_SCL{slash}CAN1_RX-Pad69)") (class "Default")
      (node (ref "STR_STM32F4DISCOVERY") (pin "69") (pinfunction "PB8/TIM4_CH3/SDIO_D4/TIM10_CH1/DCMI_D6/OTG_FS_SCL/ETH_MII_TXD3/I2C1_SCL/CAN1_RX_69") (pintype "passive+no_connect"))
    )
    (net (code "103") (name "unconnected-(STR_STM32F4DISCOVERY-PC0{slash}OTG_HS_ULPI_STP{slash}ADC123_IN10-Pad8)") (class "Default")
      (node (ref "STR_STM32F4DISCOVERY") (pin "8") (pinfunction "PC0/OTG_HS_ULPI_STP/ADC123_IN10_8") (pintype "passive+no_connect"))
    )
    (net (code "104") (name "unconnected-(STR_STM32F4DISCOVERY-PC12{slash}UART5_TX{slash}SDIO_CK{slash}DCMI_D9{slash}SPI3_MOSI{slash}I2S3_SD{slash}USART3_CK-Pad85)") (class "Default")
      (node (ref "STR_STM32F4DISCOVERY") (pin "85") (pinfunction "PC12/UART5_TX/SDIO_CK/DCMI_D9/SPI3_MOSI/I2S3_SD/USART3_CK_85") (pintype "passive"))
    )
    (net (code "105") (name "unconnected-(STR_STM32F4DISCOVERY-PC14{slash}OSC32_IN-Pad59)") (class "Default")
      (node (ref "STR_STM32F4DISCOVERY") (pin "59") (pinfunction "PC14/OSC32_IN_59") (pintype "passive+no_connect"))
    )
    (net (code "106") (name "unconnected-(STR_STM32F4DISCOVERY-PC15{slash}OSC32_OUT-Pad60)") (class "Default")
      (node (ref "STR_STM32F4DISCOVERY") (pin "60") (pinfunction "PC15/OSC32_OUT_60") (pintype "passive+no_connect"))
    )
    (net (code "107") (name "unconnected-(STR_STM32F4DISCOVERY-PD6{slash}FSMC_NWAIT{slash}USART2_RX-Pad80)") (class "Default")
      (node (ref "STR_STM32F4DISCOVERY") (pin "80") (pinfunction "PD6/FSMC_NWAIT/USART2_RX_80") (pintype "passive"))
    )
    (net (code "108") (name "unconnected-(STR_STM32F4DISCOVERY-PD7{slash}USART2_CK{slash}FSMC_NE1{slash}FSMC_NCE2-Pad77)") (class "Default")
      (node (ref "STR_STM32F4DISCOVERY") (pin "77") (pinfunction "PD7/USART2_CK/FSMC_NE1/FSMC_NCE2_77") (pintype "passive"))
    )
    (net (code "109") (name "unconnected-(STR_STM32F4DISCOVERY-PE0{slash}TIM4_ETR{slash}FSMC_NBL0{slash}DCMI_D2-Pad67)") (class "Default")
      (node (ref "STR_STM32F4DISCOVERY") (pin "67") (pinfunction "PE0/TIM4_ETR/FSMC_NBL0/DCMI_D2_67") (pintype "passive+no_connect"))
    )
    (net (code "110") (name "unconnected-(STR_STM32F4DISCOVERY-PE1{slash}FSMC_NBL1{slash}DCMI_D3-Pad68)") (class "Default")
      (node (ref "STR_STM32F4DISCOVERY") (pin "68") (pinfunction "PE1/FSMC_NBL1/DCMI_D3_68") (pintype "passive+no_connect"))
    )
    (net (code "111") (name "unconnected-(STR_STM32F4DISCOVERY-PE2{slash}TRACECLK{slash}FSMC_A23{slash}ETH_MII_TXD3-Pad65)") (class "Default")
      (node (ref "STR_STM32F4DISCOVERY") (pin "65") (pinfunction "PE2/TRACECLK/FSMC_A23/ETH_MII_TXD3_65") (pintype "passive+no_connect"))
    )
    (net (code "112") (name "unconnected-(STR_STM32F4DISCOVERY-PE3{slash}TRACED0{slash}FSMC_A19-Pad66)") (class "Default")
      (node (ref "STR_STM32F4DISCOVERY") (pin "66") (pinfunction "PE3/TRACED0/FSMC_A19_66") (pintype "passive+no_connect"))
    )
    (net (code "113") (name "unconnected-(STR_STM32F4DISCOVERY-PE4{slash}TRACED1{slash}FSMC_A20{slash}DCMI_D4-Pad63)") (class "Default")
      (node (ref "STR_STM32F4DISCOVERY") (pin "63") (pinfunction "PE4/TRACED1/FSMC_A20/DCMI_D4_63") (pintype "passive+no_connect"))
    )
    (net (code "114") (name "unconnected-(STR_STM32F4DISCOVERY-PE5{slash}TRACED2{slash}FSMC_A21{slash}TIM9_CH1{slash}DCMI_D6-Pad64)") (class "Default")
      (node (ref "STR_STM32F4DISCOVERY") (pin "64") (pinfunction "PE5/TRACED2/FSMC_A21/TIM9_CH1/DCMI_D6_64") (pintype "passive+no_connect"))
    )
    (net (code "115") (name "unconnected-(STR_STM32F4DISCOVERY-PE6{slash}TRACED3{slash}FSMC_A22{slash}TIM9_CH2{slash}DCMI_D7-Pad61)") (class "Default")
      (node (ref "STR_STM32F4DISCOVERY") (pin "61") (pinfunction "PE6/TRACED3/FSMC_A22/TIM9_CH2/DCMI_D7_61") (pintype "passive+no_connect"))
    )
    (net (code "116") (name "unconnected-(STR_STM32F4DISCOVERY-PE11{slash}FSMC_D8{slash}TIM1_CH2-Pad29)") (class "Default")
      (node (ref "STR_STM32F4DISCOVERY") (pin "29") (pinfunction "PE11/FSMC_D8/TIM1_CH2_29") (pintype "passive"))
    )
    (net (code "117") (name "unconnected-(STR_STM32F4DISCOVERY-PE12{slash}FSMC_D9{slash}TIM1_CH3N-Pad30)") (class "Default")
      (node (ref "STR_STM32F4DISCOVERY") (pin "30") (pinfunction "PE12/FSMC_D9/TIM1_CH3N_30") (pintype "passive"))
    )
    (net (code "118") (name "unconnected-(STR_STM32F4DISCOVERY-PE13{slash}FSMC_D10{slash}TIM1_CH3-Pad31)") (class "Default")
      (node (ref "STR_STM32F4DISCOVERY") (pin "31") (pinfunction "PE13/FSMC_D10/TIM1_CH3_31") (pintype "passive"))
    )
    (net (code "119") (name "unconnected-(STR_STM32F4DISCOVERY-PE14{slash}FSMC_D11{slash}TIM1_CH4-Pad32)") (class "Default")
      (node (ref "STR_STM32F4DISCOVERY") (pin "32") (pinfunction "PE14/FSMC_D11/TIM1_CH4_32") (pintype "passive"))
    )
    (net (code "120") (name "unconnected-(STR_STM32F4DISCOVERY-PE15{slash}FSMC_D12{slash}TIM1_BKIN-Pad33)") (class "Default")
      (node (ref "STR_STM32F4DISCOVERY") (pin "33") (pinfunction "PE15/FSMC_D12/TIM1_BKIN_33") (pintype "passive"))
    )
    (net (code "121") (name "unconnected-(STR_STM32F4DISCOVERY-PH0{slash}OSC_IN-Pad57)") (class "Default")
      (node (ref "STR_STM32F4DISCOVERY") (pin "57") (pinfunction "PH0/OSC_IN_57") (pintype "passive+no_connect"))
    )
    (net (code "122") (name "unconnected-(STR_STM32F4DISCOVERY-PH1{slash}OSC_OUT-Pad58)") (class "Default")
      (node (ref "STR_STM32F4DISCOVERY") (pin "58") (pinfunction "PH1/OSC_OUT_58") (pintype "passive+no_connect"))
    )
    (net (code "123") (name "unconnected-(STR_STM32F4DISCOVERY-VDD-Pad3)") (class "Default")
      (node (ref "STR_STM32F4DISCOVERY") (pin "3") (pinfunction "VDD_3") (pintype "passive+no_connect"))
    )
    (net (code "124") (name "unconnected-(STR_STM32F4DISCOVERY-VDD-Pad4)") (class "Default")
      (node (ref "STR_STM32F4DISCOVERY") (pin "4") (pinfunction "VDD_4") (pintype "passive+no_connect"))
    )
    (net (code "125") (name "unconnected-(STR_STM32F4DISCOVERY-VDD-Pad72)") (class "Default")
      (node (ref "STR_STM32F4DISCOVERY") (pin "72") (pinfunction "VDD_72") (pintype "passive+no_connect"))
    )
    (net (code "126") (name "unconnected-(STR_Ucan-VREF-Pad5)") (class "Default")
      (node (ref "STR_Ucan") (pin "5") (pinfunction "VREF_5") (pintype "output"))
    )
  )
)
